# 2_byte_output.net
KiCad netlist of a schematic drawn in EAGLE
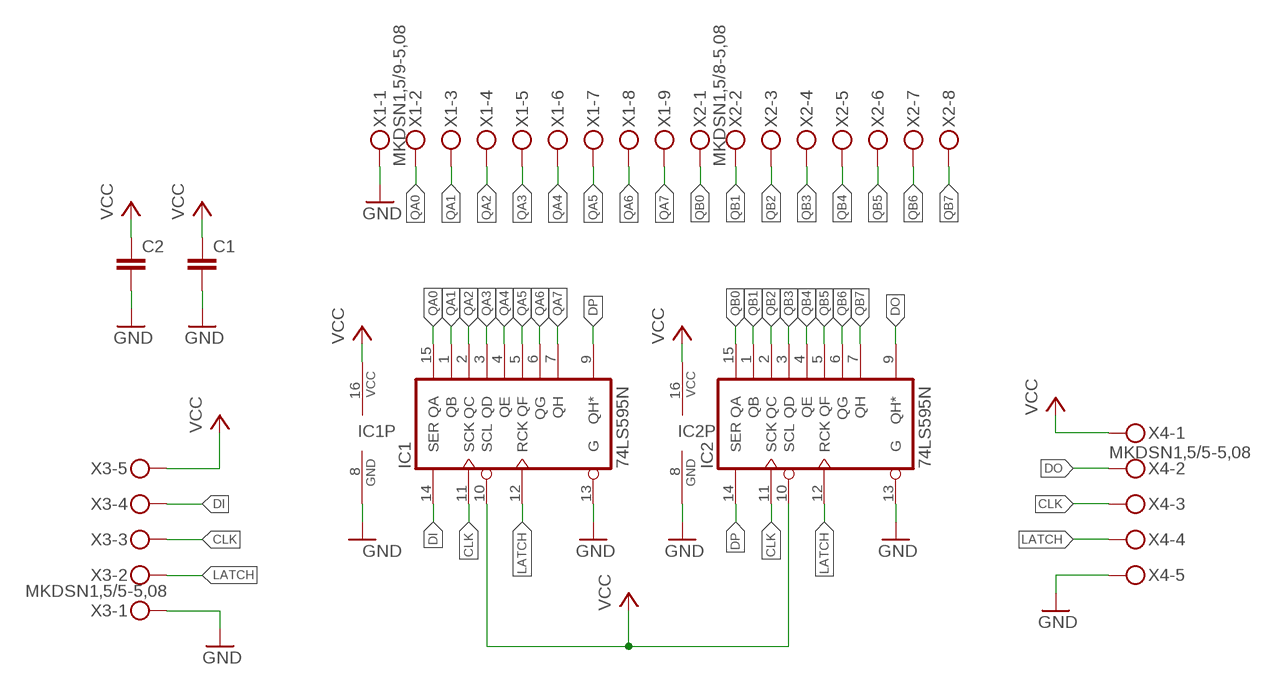
[diagram p0: schematic, sheet 1]

(export (version "E")
  (design (tool "Eeschema 10.0.6"))
  (components
    (comp (ref "C1")
      (value "C-EU050-035X075")
      (footprint "eagle-import:C050-035X075")
      (libsource (lib "eagle-import") (part "C-EU050-035X075"))
    )
    (comp (ref "C2")
      (value "C-EU050-035X075")
      (footprint "eagle-import:C050-035X075")
      (libsource (lib "eagle-import") (part "C-EU050-035X075"))
    )
    (comp (ref "IC1")
      (value "74LS595N")
      (footprint "eagle-import:DIL16")
      (libsource (lib "eagle-import") (part "74595NLS"))
    )
    (comp (ref "IC2")
      (value "74LS595N")
      (footprint "eagle-import:DIL16")
      (libsource (lib "eagle-import") (part "74595NLS"))
    )
    (comp (ref "X1")
      (value "MKDSN1,5/9-5,08")
      (footprint "eagle-import:MKDSN1,5_9-5,08")
      (libsource (lib "eagle-import") (part "MKDSN1,5/9-5,08"))
    )
    (comp (ref "X2")
      (value "MKDSN1,5/8-5,08")
      (footprint "eagle-import:MKDSN1,5_8-5,08")
      (libsource (lib "eagle-import") (part "MKDSN1,5/8-5,08"))
    )
    (comp (ref "X3")
      (value "MKDSN1,5/5-5,08")
      (footprint "eagle-import:MKDSN1,5_5-5,08")
      (libsource (lib "eagle-import") (part "MKDSN1,5/5-5,08"))
    )
    (comp (ref "X4")
      (value "MKDSN1,5/5-5,08")
      (footprint "eagle-import:MKDSN1,5_5-5,08")
      (libsource (lib "eagle-import") (part "MKDSN1,5/5-5,08"))
    )
  )
  (nets
    (net (code "1") (name "CLK") (class "Default")
      (node (ref "IC1") (pin "11") (pinfunction "SCK_11") (pintype "input"))
      (node (ref "IC2") (pin "11") (pinfunction "SCK_11") (pintype "input"))
      (node (ref "X3") (pin "3") (pinfunction "KL_3") (pintype "passive"))
      (node (ref "X4") (pin "3") (pinfunction "KL_3") (pintype "passive"))
    )
    (net (code "2") (name "DI") (class "Default")
      (node (ref "IC1") (pin "14") (pinfunction "SER_14") (pintype "input"))
      (node (ref "X3") (pin "4") (pinfunction "KL_4") (pintype "passive"))
    )
    (net (code "3") (name "DO") (class "Default")
      (node (ref "IC2") (pin "9") (pinfunction "QH*_9") (pintype "tri_state"))
      (node (ref "X4") (pin "2") (pinfunction "KL_2") (pintype "passive"))
    )
    (net (code "4") (name "DP") (class "Default")
      (node (ref "IC1") (pin "9") (pinfunction "QH*_9") (pintype "tri_state"))
      (node (ref "IC2") (pin "14") (pinfunction "SER_14") (pintype "input"))
    )
    (net (code "5") (name "GND") (class "Default")
      (node (ref "C1") (pin "2") (pinfunction "2_2") (pintype "passive"))
      (node (ref "C2") (pin "2") (pinfunction "2_2") (pintype "passive"))
      (node (ref "IC1") (pin "13") (pinfunction "G_13") (pintype "input"))
      (node (ref "IC1") (pin "8") (pinfunction "GND_8") (pintype "power_in"))
      (node (ref "IC2") (pin "13") (pinfunction "G_13") (pintype "input"))
      (node (ref "IC2") (pin "8") (pinfunction "GND_8") (pintype "power_in"))
      (node (ref "X1") (pin "1") (pinfunction "KL_1") (pintype "passive"))
      (node (ref "X3") (pin "1") (pinfunction "KL_1") (pintype "passive"))
      (node (ref "X4") (pin "5") (pinfunction "KL_5") (pintype "passive"))
    )
    (net (code "6") (name "LATCH") (class "Default")
      (node (ref "IC1") (pin "12") (pinfunction "RCK_12") (pintype "input"))
      (node (ref "IC2") (pin "12") (pinfunction "RCK_12") (pintype "input"))
      (node (ref "X3") (pin "2") (pinfunction "KL_2") (pintype "passive"))
      (node (ref "X4") (pin "4") (pinfunction "KL_4") (pintype "passive"))
    )
    (net (code "7") (name "QA0") (class "Default")
      (node (ref "IC1") (pin "15") (pinfunction "QA_15") (pintype "tri_state"))
      (node (ref "X1") (pin "2") (pinfunction "KL_2") (pintype "passive"))
    )
    (net (code "8") (name "QA1") (class "Default")
      (node (ref "IC1") (pin "1") (pinfunction "QB_1") (pintype "tri_state"))
      (node (ref "X1") (pin "3") (pinfunction "KL_3") (pintype "passive"))
    )
    (net (code "9") (name "QA2") (class "Default")
      (node (ref "IC1") (pin "2") (pinfunction "QC_2") (pintype "tri_state"))
      (node (ref "X1") (pin "4") (pinfunction "KL_4") (pintype "passive"))
    )
    (net (code "10") (name "QA3") (class "Default")
      (node (ref "IC1") (pin "3") (pinfunction "QD_3") (pintype "tri_state"))
      (node (ref "X1") (pin "5") (pinfunction "KL_5") (pintype "passive"))
    )
    (net (code "11") (name "QA4") (class "Default")
      (node (ref "IC1") (pin "4") (pinfunction "QE_4") (pintype "tri_state"))
      (node (ref "X1") (pin "6") (pinfunction "KL_6") (pintype "passive"))
    )
    (net (code "12") (name "QA5") (class "Default")
      (node (ref "IC1") (pin "5") (pinfunction "QF_5") (pintype "tri_state"))
      (node (ref "X1") (pin "7") (pinfunction "KL_7") (pintype "passive"))
    )
    (net (code "13") (name "QA6") (class "Default")
      (node (ref "IC1") (pin "6") (pinfunction "QG_6") (pintype "tri_state"))
      (node (ref "X1") (pin "8") (pinfunction "KL_8") (pintype "passive"))
    )
    (net (code "14") (name "QA7") (class "Default")
      (node (ref "IC1") (pin "7") (pinfunction "QH_7") (pintype "tri_state"))
      (node (ref "X1") (pin "9") (pinfunction "KL_9") (pintype "passive"))
    )
    (net (code "15") (name "QB0") (class "Default")
      (node (ref "IC2") (pin "15") (pinfunction "QA_15") (pintype "tri_state"))
      (node (ref "X2") (pin "1") (pinfunction "KL_1") (pintype "passive"))
    )
    (net (code "16") (name "QB1") (class "Default")
      (node (ref "IC2") (pin "1") (pinfunction "QB_1") (pintype "tri_state"))
      (node (ref "X2") (pin "2") (pinfunction "KL_2") (pintype "passive"))
    )
    (net (code "17") (name "QB2") (class "Default")
      (node (ref "IC2") (pin "2") (pinfunction "QC_2") (pintype "tri_state"))
      (node (ref "X2") (pin "3") (pinfunction "KL_3") (pintype "passive"))
    )
    (net (code "18") (name "QB3") (class "Default")
      (node (ref "IC2") (pin "3") (pinfunction "QD_3") (pintype "tri_state"))
      (node (ref "X2") (pin "4") (pinfunction "KL_4") (pintype "passive"))
    )
    (net (code "19") (name "QB4") (class "Default")
      (node (ref "IC2") (pin "4") (pinfunction "QE_4") (pintype "tri_state"))
      (node (ref "X2") (pin "5") (pinfunction "KL_5") (pintype "passive"))
    )
    (net (code "20") (name "QB5") (class "Default")
      (node (ref "IC2") (pin "5") (pinfunction "QF_5") (pintype "tri_state"))
      (node (ref "X2") (pin "6") (pinfunction "KL_6") (pintype "passive"))
    )
    (net (code "21") (name "QB6") (class "Default")
      (node (ref "IC2") (pin "6") (pinfunction "QG_6") (pintype "tri_state"))
      (node (ref "X2") (pin "7") (pinfunction "KL_7") (pintype "passive"))
    )
    (net (code "22") (name "QB7") (class "Default")
      (node (ref "IC2") (pin "7") (pinfunction "QH_7") (pintype "tri_state"))
      (node (ref "X2") (pin "8") (pinfunction "KL_8") (pintype "passive"))
    )
    (net (code "23") (name "VCC") (class "Default")
      (node (ref "C1") (pin "1") (pinfunction "1_1") (pintype "passive"))
      (node (ref "C2") (pin "1") (pinfunction "1_1") (pintype "passive"))
      (node (ref "IC1") (pin "10") (pinfunction "SCL_10") (pintype "input"))
      (node (ref "IC1") (pin "16") (pinfunction "VCC_16") (pintype "power_in"))
      (node (ref "IC2") (pin "10") (pinfunction "SCL_10") (pintype "input"))
      (node (ref "IC2") (pin "16") (pinfunction "VCC_16") (pintype "power_in"))
      (node (ref "X3") (pin "5") (pinfunction "KL_5") (pintype "passive"))
      (node (ref "X4") (pin "1") (pinfunction "KL_1") (pintype "passive"))
    )
  )
)
